# YoctoBob_LPC1102.net
KiCad netlist of a schematic drawn in Altium Designer
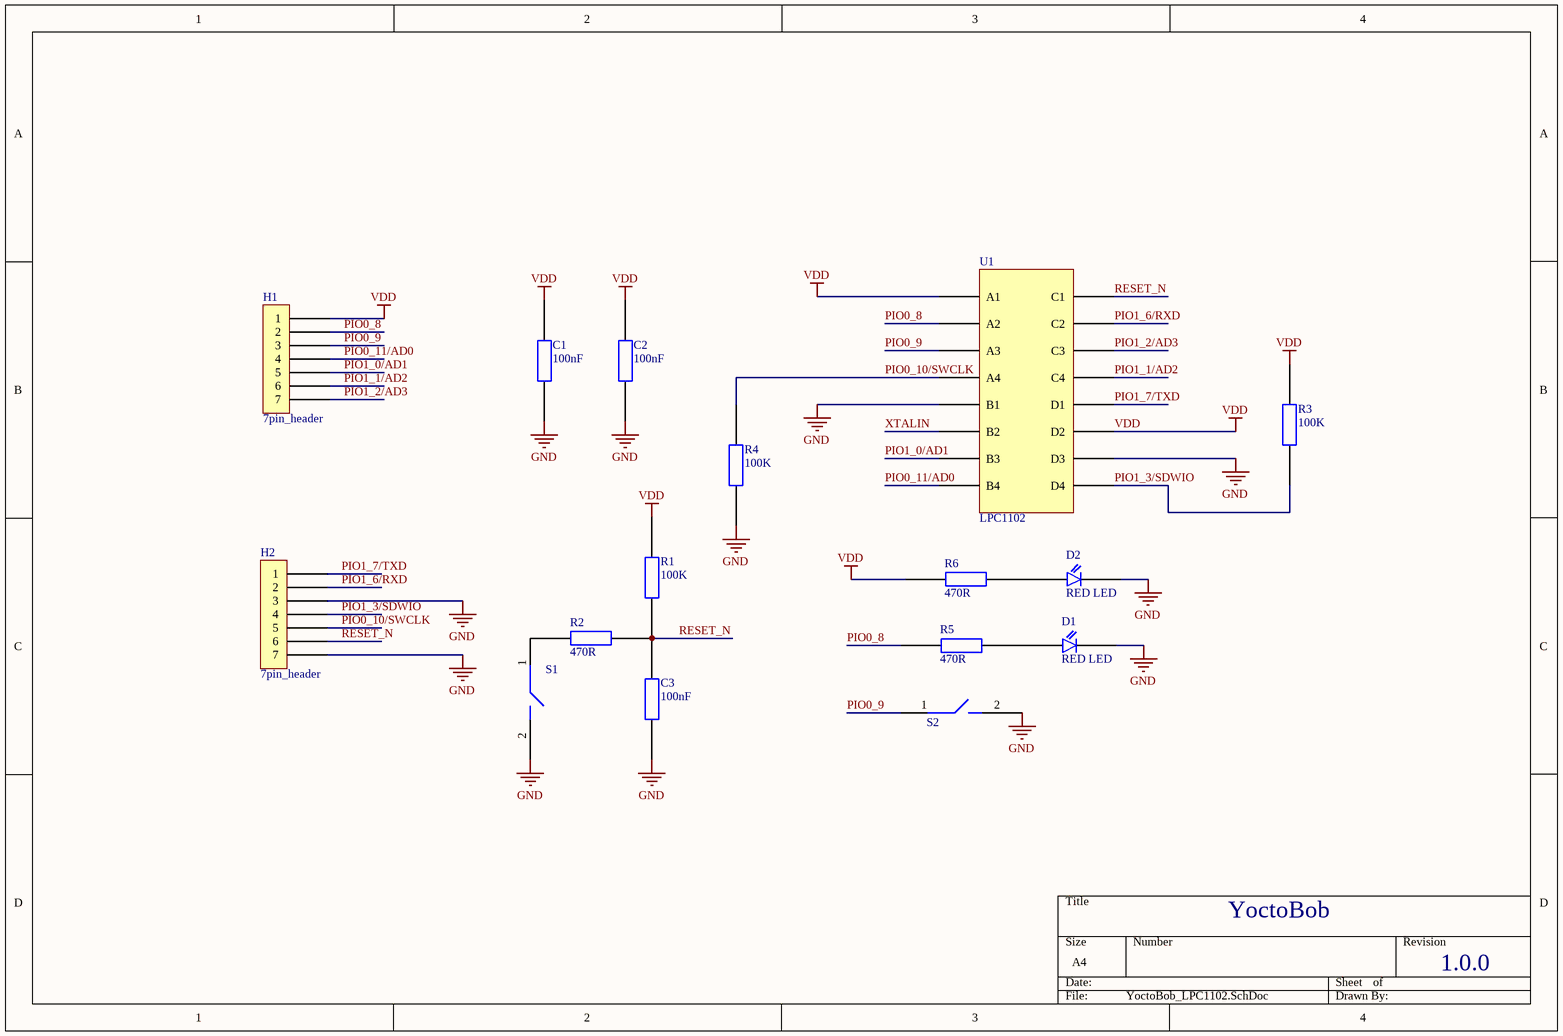
[diagram p0: YoctoBob_LPC1102.SchDoc]

(export (version "E")
  (design (tool "Eeschema 10.0.6"))
  (components
    (comp (ref "C1") (value "100nF") (footprint "C0805") (libsource (lib "Component_Library") (part "100nF")))
    (comp (ref "C2") (value "100nF") (footprint "C0805") (libsource (lib "Component_Library") (part "100nF")))
    (comp (ref "C3") (value "100nF") (footprint "C0805") (libsource (lib "Component_Library") (part "100nF")))
    (comp (ref "D1")
      (value "RED LED")
      (footprint "RED_LED_0805")
      (libsource (lib "Component_Library") (part "RED LED"))
    )
    (comp (ref "D2")
      (value "RED LED")
      (footprint "RED_LED_0805")
      (libsource (lib "Component_Library") (part "RED LED"))
    )
    (comp (ref "H1")
      (value "7pin_header")
      (footprint "HDR1X7")
      (libsource (lib "Component_Library") (part "7pin_header"))
    )
    (comp (ref "H2")
      (value "7pin_header")
      (footprint "HDR1X7")
      (libsource (lib "Component_Library") (part "7pin_header"))
    )
    (comp (ref "R1") (value "100K") (footprint "R0805") (libsource (lib "Component_Library") (part "100K")))
    (comp (ref "R2") (value "470R") (footprint "R0805") (libsource (lib "Component_Library") (part "470R")))
    (comp (ref "R3") (value "100K") (footprint "R0805") (libsource (lib "Component_Library") (part "100K")))
    (comp (ref "R4") (value "100K") (footprint "R0805") (libsource (lib "Component_Library") (part "100K")))
    (comp (ref "R5") (value "470R") (footprint "R0805") (libsource (lib "Component_Library") (part "470R")))
    (comp (ref "R6") (value "470R") (footprint "R0805") (libsource (lib "Component_Library") (part "470R")))
    (comp (ref "S1")
      (value "switch")
      (footprint "SWITCH_B3U-1000P")
      (libsource (lib "Component_Library") (part "switch"))
    )
    (comp (ref "S2")
      (value "switch")
      (footprint "SWITCH_B3U-1000P")
      (libsource (lib "Component_Library") (part "switch"))
    )
    (comp (ref "U1") (value "LPC1102") (libsource (lib "Component_Library") (part "LPC1102")))
  )
  (nets
    (net (code "1") (name "/PIO0_8") (class "Default")
      (node (ref "H1") (pin "2") (pinfunction "2_2") (pintype "passive"))
      (node (ref "R5") (pin "1") (pinfunction "1_1") (pintype "passive"))
      (node (ref "U1") (pin "A2") (pinfunction "A2_A2") (pintype "passive"))
    )
    (net (code "2") (name "/PIO0_9") (class "Default")
      (node (ref "H1") (pin "3") (pinfunction "3_3") (pintype "passive"))
      (node (ref "S2") (pin "1") (pinfunction "1_1") (pintype "passive"))
      (node (ref "U1") (pin "A3") (pinfunction "A3_A3") (pintype "passive"))
    )
    (net (code "3") (name "/PIO0_10{slash}SWCLK") (class "Default")
      (node (ref "H2") (pin "5") (pinfunction "5_5") (pintype "passive"))
      (node (ref "R4") (pin "1") (pinfunction "1_1") (pintype "passive"))
      (node (ref "U1") (pin "A4") (pinfunction "A4_A4") (pintype "passive"))
    )
    (net (code "4") (name "/PIO0_11{slash}AD0") (class "Default")
      (node (ref "H1") (pin "4") (pinfunction "4_4") (pintype "passive"))
      (node (ref "U1") (pin "B4") (pinfunction "B4_B4") (pintype "passive"))
    )
    (net (code "5") (name "/PIO1_0{slash}AD1") (class "Default")
      (node (ref "H1") (pin "5") (pinfunction "5_5") (pintype "passive"))
      (node (ref "U1") (pin "B3") (pinfunction "B3_B3") (pintype "passive"))
    )
    (net (code "6") (name "/PIO1_1{slash}AD2") (class "Default")
      (node (ref "H1") (pin "6") (pinfunction "6_6") (pintype "passive"))
      (node (ref "U1") (pin "C4") (pinfunction "C4_C4") (pintype "passive"))
    )
    (net (code "7") (name "/PIO1_2{slash}AD3") (class "Default")
      (node (ref "H1") (pin "7") (pinfunction "7_7") (pintype "passive"))
      (node (ref "U1") (pin "C3") (pinfunction "C3_C3") (pintype "passive"))
    )
    (net (code "8") (name "/PIO1_3{slash}SDWIO") (class "Default")
      (node (ref "H2") (pin "4") (pinfunction "4_4") (pintype "passive"))
      (node (ref "R3") (pin "2") (pinfunction "2_2") (pintype "passive"))
      (node (ref "U1") (pin "D4") (pinfunction "D4_D4") (pintype "passive"))
    )
    (net (code "9") (name "/PIO1_6{slash}RXD") (class "Default")
      (node (ref "H2") (pin "2") (pinfunction "2_2") (pintype "passive"))
      (node (ref "U1") (pin "C2") (pinfunction "C2_C2") (pintype "passive"))
    )
    (net (code "10") (name "/PIO1_7{slash}TXD") (class "Default")
      (node (ref "H2") (pin "1") (pinfunction "1_1") (pintype "passive"))
      (node (ref "U1") (pin "D1") (pinfunction "D1_D1") (pintype "passive"))
    )
    (net (code "11") (name "/RESET_N") (class "Default")
      (node (ref "C3") (pin "2") (pinfunction "2_2") (pintype "passive"))
      (node (ref "H2") (pin "6") (pinfunction "6_6") (pintype "passive"))
      (node (ref "R1") (pin "1") (pinfunction "1_1") (pintype "passive"))
      (node (ref "R2") (pin "2") (pinfunction "2_2") (pintype "passive"))
      (node (ref "U1") (pin "C1") (pinfunction "C1_C1") (pintype "passive"))
    )
    (net (code "12") (name "/XTALIN") (class "Default")
      (node (ref "U1") (pin "B2") (pinfunction "B2_B2") (pintype "passive"))
    )
    (net (code "13") (name "GND") (class "Default")
      (node (ref "C1") (pin "1") (pinfunction "1_1") (pintype "passive"))
      (node (ref "C2") (pin "1") (pinfunction "1_1") (pintype "passive"))
      (node (ref "C3") (pin "1") (pinfunction "1_1") (pintype "passive"))
      (node (ref "D1") (pin "2") (pinfunction "2_2") (pintype "passive"))
      (node (ref "D2") (pin "2") (pinfunction "2_2") (pintype "passive"))
      (node (ref "H2") (pin "3") (pinfunction "3_3") (pintype "passive"))
      (node (ref "H2") (pin "7") (pinfunction "7_7") (pintype "passive"))
      (node (ref "R4") (pin "2") (pinfunction "2_2") (pintype "passive"))
      (node (ref "S1") (pin "2") (pinfunction "2_2") (pintype "passive"))
      (node (ref "S2") (pin "2") (pinfunction "2_2") (pintype "passive"))
      (node (ref "U1") (pin "B1") (pinfunction "B1_B1") (pintype "passive"))
      (node (ref "U1") (pin "D3") (pinfunction "D3_D3") (pintype "passive"))
    )
    (net (code "14") (name "Net-(D1-Pad1)") (class "Default")
      (node (ref "D1") (pin "1") (pinfunction "1_1") (pintype "passive"))
      (node (ref "R5") (pin "2") (pinfunction "2_2") (pintype "passive"))
    )
    (net (code "15") (name "Net-(D2-Pad1)") (class "Default")
      (node (ref "D2") (pin "1") (pinfunction "1_1") (pintype "passive"))
      (node (ref "R6") (pin "2") (pinfunction "2_2") (pintype "passive"))
    )
    (net (code "16") (name "Net-(R2-Pad1)") (class "Default")
      (node (ref "R2") (pin "1") (pinfunction "1_1") (pintype "passive"))
      (node (ref "S1") (pin "1") (pinfunction "1_1") (pintype "passive"))
    )
    (net (code "17") (name "VDD") (class "Default")
      (node (ref "C1") (pin "2") (pinfunction "2_2") (pintype "passive"))
      (node (ref "C2") (pin "2") (pinfunction "2_2") (pintype "passive"))
      (node (ref "H1") (pin "1") (pinfunction "1_1") (pintype "passive"))
      (node (ref "R1") (pin "2") (pinfunction "2_2") (pintype "passive"))
      (node (ref "R3") (pin "1") (pinfunction "1_1") (pintype "passive"))
      (node (ref "R6") (pin "1") (pinfunction "1_1") (pintype "passive"))
      (node (ref "U1") (pin "A1") (pinfunction "A1_A1") (pintype "passive"))
      (node (ref "U1") (pin "D2") (pinfunction "D2_D2") (pintype "passive"))
    )
  )
)
